# PWR.net
KiCad netlist of a schematic drawn in Altium Designer
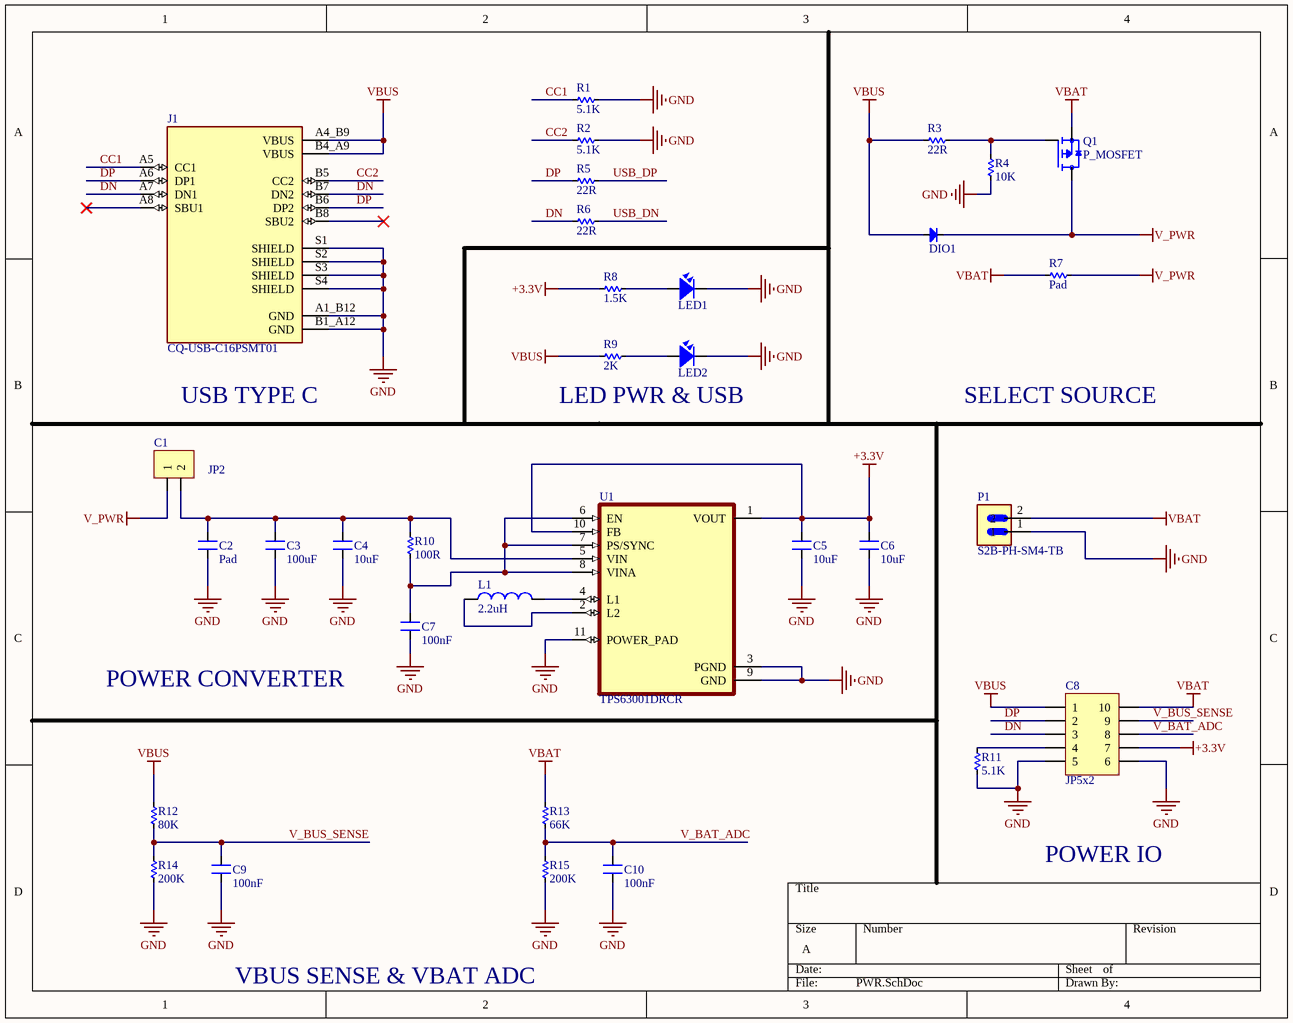
[diagram p0: PWR.SchDoc]

(export (version "E")
  (design (tool "Eeschema 10.0.6"))
  (components
    (comp (ref "C1")
      (value "JP2")
      (footprint "JP2-CLOSED")
      (description "WR-PHD 2.54 mm Angled Socket Header")
      (fields
        (field (name "MANUFACTURER") "Würth Elektronik eiSos GmbH")
        (field (name "PARTNO") "613002143121")
        (field (name "CREATED BY") "Karrer Zheng")
      )
      (libsource (lib "DATN_LIB") (part "JP2"))
    )
    (comp (ref "C2") (value "Pad") (footprint "PAD-SMD-1206") (libsource (lib "DATN_LIB") (part "Cap-SMD")))
    (comp (ref "C3") (value "100uF") (footprint "CN-SMD-1206") (libsource (lib "DATN_LIB") (part "Cap-SMD")))
    (comp (ref "C4") (value "10uF") (footprint "CN-SMD-1206") (libsource (lib "DATN_LIB") (part "Cap-SMD")))
    (comp (ref "C5") (value "10uF") (footprint "CN-SMD-1206") (libsource (lib "DATN_LIB") (part "Cap-SMD")))
    (comp (ref "C6") (value "10uF") (footprint "CN-SMD-1206") (libsource (lib "DATN_LIB") (part "Cap-SMD")))
    (comp (ref "C7") (value "100nF") (footprint "CN-SMD-0603") (libsource (lib "DATN_LIB") (part "Cap-SMD")))
    (comp (ref "C8")
      (value "JP5x2")
      (footprint "JP5-D2T")
      (description "WR-PHD 2.54 mm Dual Socket Header")
      (fields
        (field (name "MANUFACTURER") "Würth Elektronik eiSos GmbH")
        (field (name "PARTNO") "61301021821")
        (field (name "CREATED BY") "Karrer Zheng")
      )
      (libsource (lib "DATN_LIB") (part "JP5x2"))
    )
    (comp (ref "C9") (value "100nF") (footprint "CN-SMD-0603") (libsource (lib "DATN_LIB") (part "Cap-SMD")))
    (comp (ref "C10") (value "100nF") (footprint "CN-SMD-0603") (libsource (lib "DATN_LIB") (part "Cap-SMD")))
    (comp (ref "DIO1")
      (value "Diode SMD")
      (footprint "DIO-SMD-123")
      (description "Default Diode")
      (fields (field (name "PUBLISHER") "Altium Limited"))
      (libsource (lib "DATN_LIB") (part "Diode SMD"))
    )
    (comp (ref "J1")
      (value "CQ-USB-C16PSMT01")
      (footprint "SHENZHEN-CHUANGQIN-TECHNOLOGY_CQ-USB-C16PSMT01")
      (description "C Type USB Type-C Female Plug 16 Pin Connector Power Charger Jack Port")
      (fields (field (name "MF") "Shenzen Chuangqin Technology"))
      (libsource (lib "DATN_LIB") (part "CQ-USB-C16PSMT01"))
    )
    (comp (ref "L1")
      (value "2.2uH")
      (footprint "INDC6060X300")
      (description "INDUCTOR wire-wound")
      (fields (field (name "MP") "LQW2BAN68NG00L"))
      (libsource (lib "DATN_LIB") (part "SMD-Wire-Inductor"))
    )
    (comp (ref "LED1")
      (value "LED GREEN")
      (footprint "LED-0805-Green")
      (libsource (lib "DATN_LIB") (part "LED SMD"))
    )
    (comp (ref "LED2")
      (value "LED GREEN")
      (footprint "LED-0805-Blue")
      (libsource (lib "DATN_LIB") (part "LED SMD"))
    )
    (comp (ref "P1")
      (value "S2B-PH-SM4-TB")
      (footprint "JST_S2B-PH-SM4-TB")
      (description "Connector Header Surface Mount, Right Angle 2 position 0.079 (2.00mm)")
      (fields (field (name "MF") "JST Sales"))
      (libsource (lib "DATN_LIB") (part "S2B-PH-SM4-TB"))
    )
    (comp (ref "Q1")
      (value "P_MOSFET")
      (footprint "P_MOSFET_SOT23")
      (fields (field (name "MF") "Diotec Semiconductor") (field (name "MP") "MMFTP3401"))
      (libsource (lib "DATN_LIB") (part "P_MOSFET"))
    )
    (comp (ref "R1")
      (value "5.1K")
      (footprint "RES-SMD-0603")
      (description "Resistor")
      (fields
        (field (name "MANUFACTURER") "Generic Components")
        (field (name "PUBLISHER") "Altium Hobart Technology Centre")
      )
      (libsource (lib "DATN_LIB") (part "Res-SMD"))
    )
    (comp (ref "R2")
      (value "5.1K")
      (footprint "RES-SMD-0603")
      (description "Resistor")
      (fields
        (field (name "MANUFACTURER") "Generic Components")
        (field (name "PUBLISHER") "Altium Hobart Technology Centre")
      )
      (libsource (lib "DATN_LIB") (part "Res-SMD"))
    )
    (comp (ref "R3")
      (value "22R")
      (footprint "RES-SMD-0603")
      (description "Resistor")
      (fields
        (field (name "MANUFACTURER") "Generic Components")
        (field (name "PUBLISHER") "Altium Hobart Technology Centre")
      )
      (libsource (lib "DATN_LIB") (part "Res-SMD"))
    )
    (comp (ref "R4")
      (value "10K")
      (footprint "RES-SMD-0603")
      (description "Resistor")
      (fields
        (field (name "MANUFACTURER") "Generic Components")
        (field (name "PUBLISHER") "Altium Hobart Technology Centre")
      )
      (libsource (lib "DATN_LIB") (part "Res-SMD"))
    )
    (comp (ref "R5")
      (value "22R")
      (footprint "RES-SMD-0603")
      (description "Resistor")
      (fields
        (field (name "MANUFACTURER") "Generic Components")
        (field (name "PUBLISHER") "Altium Hobart Technology Centre")
      )
      (libsource (lib "DATN_LIB") (part "Res-SMD"))
    )
    (comp (ref "R6")
      (value "22R")
      (footprint "RES-SMD-0603")
      (description "Resistor")
      (fields
        (field (name "MANUFACTURER") "Generic Components")
        (field (name "PUBLISHER") "Altium Hobart Technology Centre")
      )
      (libsource (lib "DATN_LIB") (part "Res-SMD"))
    )
    (comp (ref "R7")
      (value "Pad")
      (footprint "PAD-SMD-1206")
      (description "Resistor")
      (fields
        (field (name "MANUFACTURER") "Generic Components")
        (field (name "PUBLISHER") "Altium Hobart Technology Centre")
      )
      (libsource (lib "DATN_LIB") (part "Res-SMD"))
    )
    (comp (ref "R8")
      (value "1.5K")
      (footprint "RES-SMD-0603")
      (description "Resistor")
      (fields
        (field (name "MANUFACTURER") "Generic Components")
        (field (name "PUBLISHER") "Altium Hobart Technology Centre")
      )
      (libsource (lib "DATN_LIB") (part "Res-SMD"))
    )
    (comp (ref "R9")
      (value "2K")
      (footprint "RES-SMD-0603")
      (description "Resistor")
      (fields
        (field (name "MANUFACTURER") "Generic Components")
        (field (name "PUBLISHER") "Altium Hobart Technology Centre")
      )
      (libsource (lib "DATN_LIB") (part "Res-SMD"))
    )
    (comp (ref "R10")
      (value "100R")
      (footprint "RES-SMD-0603")
      (description "Resistor")
      (fields
        (field (name "MANUFACTURER") "Generic Components")
        (field (name "PUBLISHER") "Altium Hobart Technology Centre")
      )
      (libsource (lib "DATN_LIB") (part "Res-SMD"))
    )
    (comp (ref "R11")
      (value "5.1K")
      (footprint "RES-SMD-0603")
      (description "Resistor")
      (fields
        (field (name "MANUFACTURER") "Generic Components")
        (field (name "PUBLISHER") "Altium Hobart Technology Centre")
      )
      (libsource (lib "DATN_LIB") (part "Res-SMD"))
    )
    (comp (ref "R12")
      (value "80K")
      (footprint "RES-SMD-0603")
      (description "Resistor")
      (fields
        (field (name "MANUFACTURER") "Generic Components")
        (field (name "PUBLISHER") "Altium Hobart Technology Centre")
      )
      (libsource (lib "DATN_LIB") (part "Res-SMD"))
    )
    (comp (ref "R13")
      (value "66K")
      (footprint "RES-SMD-0603")
      (description "Resistor")
      (fields
        (field (name "MANUFACTURER") "Generic Components")
        (field (name "PUBLISHER") "Altium Hobart Technology Centre")
      )
      (libsource (lib "DATN_LIB") (part "Res-SMD"))
    )
    (comp (ref "R14")
      (value "200K")
      (footprint "RES-SMD-0603")
      (description "Resistor")
      (fields
        (field (name "MANUFACTURER") "Generic Components")
        (field (name "PUBLISHER") "Altium Hobart Technology Centre")
      )
      (libsource (lib "DATN_LIB") (part "Res-SMD"))
    )
    (comp (ref "R15")
      (value "200K")
      (footprint "RES-SMD-0603")
      (description "Resistor")
      (fields
        (field (name "MANUFACTURER") "Generic Components")
        (field (name "PUBLISHER") "Altium Hobart Technology Centre")
      )
      (libsource (lib "DATN_LIB") (part "Res-SMD"))
    )
    (comp (ref "U1")
      (value "TPS63001DRCR")
      (footprint "VREG_V62/16624-01YE")
      (description "96% Buck-Boost Converter with 1.7A Current Switches, 3.3V fixed Output voltage in 3x3 QFN")
      (fields (field (name "MF") "Texas Instruments"))
      (libsource (lib "DATN_LIB") (part "TPS63001DRCR"))
    )
  )
  (nets
    (net (code "1") (name "+3.3V") (class "Default")
      (node (ref "C5") (pin "2") (pinfunction "2_2") (pintype "passive"))
      (node (ref "C6") (pin "2") (pinfunction "2_2") (pintype "passive"))
      (node (ref "C8") (pin "7") (pinfunction "7_7") (pintype "passive"))
      (node (ref "R8") (pin "2") (pinfunction "2_2") (pintype "passive"))
      (node (ref "U1") (pin "1") (pinfunction "VOUT_1") (pintype "power_in"))
      (node (ref "U1") (pin "10") (pinfunction "FB_10") (pintype "input"))
    )
    (net (code "2") (name "/CC1") (class "Default")
      (node (ref "J1") (pin "A5") (pinfunction "CC1_A5") (pintype "bidirectional"))
      (node (ref "R1") (pin "2") (pinfunction "2_2") (pintype "passive"))
    )
    (net (code "3") (name "/CC2") (class "Default")
      (node (ref "J1") (pin "B5") (pinfunction "CC2_B5") (pintype "bidirectional"))
      (node (ref "R2") (pin "2") (pinfunction "2_2") (pintype "passive"))
    )
    (net (code "4") (name "/DN") (class "Default")
      (node (ref "C8") (pin "3") (pinfunction "3_3") (pintype "passive"))
      (node (ref "J1") (pin "A7") (pinfunction "DN1_A7") (pintype "bidirectional"))
      (node (ref "J1") (pin "B7") (pinfunction "DN2_B7") (pintype "bidirectional"))
      (node (ref "R6") (pin "2") (pinfunction "2_2") (pintype "passive"))
    )
    (net (code "5") (name "/DP") (class "Default")
      (node (ref "C8") (pin "2") (pinfunction "2_2") (pintype "passive"))
      (node (ref "J1") (pin "A6") (pinfunction "DP1_A6") (pintype "bidirectional"))
      (node (ref "J1") (pin "B6") (pinfunction "DP2_B6") (pintype "bidirectional"))
      (node (ref "R5") (pin "2") (pinfunction "2_2") (pintype "passive"))
    )
    (net (code "6") (name "/USB_DN") (class "Default")
      (node (ref "R6") (pin "1") (pinfunction "1_1") (pintype "passive"))
    )
    (net (code "7") (name "/USB_DP") (class "Default")
      (node (ref "R5") (pin "1") (pinfunction "1_1") (pintype "passive"))
    )
    (net (code "8") (name "/V_BAT_ADC") (class "Default")
      (node (ref "C10") (pin "2") (pinfunction "2_2") (pintype "passive"))
      (node (ref "C8") (pin "8") (pinfunction "8_8") (pintype "passive"))
      (node (ref "R13") (pin "1") (pinfunction "1_1") (pintype "passive"))
      (node (ref "R15") (pin "2") (pinfunction "2_2") (pintype "passive"))
    )
    (net (code "9") (name "/V_BUS_SENSE") (class "Default")
      (node (ref "C8") (pin "9") (pinfunction "9_9") (pintype "passive"))
      (node (ref "C9") (pin "2") (pinfunction "2_2") (pintype "passive"))
      (node (ref "R12") (pin "1") (pinfunction "1_1") (pintype "passive"))
      (node (ref "R14") (pin "2") (pinfunction "2_2") (pintype "passive"))
    )
    (net (code "10") (name "GND") (class "Default")
      (node (ref "C10") (pin "1") (pinfunction "1_1") (pintype "passive"))
      (node (ref "C2") (pin "1") (pinfunction "1_1") (pintype "passive"))
      (node (ref "C3") (pin "1") (pinfunction "1_1") (pintype "passive"))
      (node (ref "C4") (pin "1") (pinfunction "1_1") (pintype "passive"))
      (node (ref "C5") (pin "1") (pinfunction "1_1") (pintype "passive"))
      (node (ref "C6") (pin "1") (pinfunction "1_1") (pintype "passive"))
      (node (ref "C7") (pin "1") (pinfunction "1_1") (pintype "passive"))
      (node (ref "C8") (pin "5") (pinfunction "5_5") (pintype "passive"))
      (node (ref "C8") (pin "6") (pinfunction "6_6") (pintype "passive"))
      (node (ref "C9") (pin "1") (pinfunction "1_1") (pintype "passive"))
      (node (ref "J1") (pin "A1_B12") (pinfunction "GND_A1_B12") (pintype "power_in"))
      (node (ref "J1") (pin "B1_A12") (pinfunction "GND_B1_A12") (pintype "power_in"))
      (node (ref "J1") (pin "S1") (pinfunction "SHIELD_S1") (pintype "passive"))
      (node (ref "J1") (pin "S2") (pinfunction "SHIELD_S2") (pintype "passive"))
      (node (ref "J1") (pin "S3") (pinfunction "SHIELD_S3") (pintype "passive"))
      (node (ref "J1") (pin "S4") (pinfunction "SHIELD_S4") (pintype "passive"))
      (node (ref "LED1") (pin "2") (pinfunction "2_2") (pintype "passive"))
      (node (ref "LED2") (pin "2") (pinfunction "2_2") (pintype "passive"))
      (node (ref "P1") (pin "1") (pinfunction "1_1") (pintype "passive"))
      (node (ref "R1") (pin "1") (pinfunction "1_1") (pintype "passive"))
      (node (ref "R11") (pin "2") (pinfunction "2_2") (pintype "passive"))
      (node (ref "R14") (pin "1") (pinfunction "1_1") (pintype "passive"))
      (node (ref "R15") (pin "1") (pinfunction "1_1") (pintype "passive"))
      (node (ref "R2") (pin "1") (pinfunction "1_1") (pintype "passive"))
      (node (ref "R4") (pin "2") (pinfunction "2_2") (pintype "passive"))
      (node (ref "U1") (pin "11") (pinfunction "POWER_PAD_11") (pintype "bidirectional"))
      (node (ref "U1") (pin "3") (pinfunction "PGND_3") (pintype "power_in"))
      (node (ref "U1") (pin "9") (pinfunction "GND_9") (pintype "power_in"))
    )
    (net (code "11") (name "Net-(C8-Pad4)") (class "Default")
      (node (ref "C8") (pin "4") (pinfunction "4_4") (pintype "passive"))
      (node (ref "R11") (pin "1") (pinfunction "1_1") (pintype "passive"))
    )
    (net (code "12") (name "Net-(LED1-Pad1)") (class "Default")
      (node (ref "LED1") (pin "1") (pinfunction "1_1") (pintype "passive"))
      (node (ref "R8") (pin "1") (pinfunction "1_1") (pintype "passive"))
    )
    (net (code "13") (name "Net-(LED2-Pad1)") (class "Default")
      (node (ref "LED2") (pin "1") (pinfunction "1_1") (pintype "passive"))
      (node (ref "R9") (pin "1") (pinfunction "1_1") (pintype "passive"))
    )
    (net (code "14") (name "Net-(Q1-G)") (class "Default")
      (node (ref "Q1") (pin "1") (pinfunction "G_1") (pintype "passive"))
      (node (ref "R3") (pin "1") (pinfunction "1_1") (pintype "passive"))
      (node (ref "R4") (pin "1") (pinfunction "1_1") (pintype "passive"))
    )
    (net (code "15") (name "Net-(U1-EN)") (class "Default")
      (node (ref "C7") (pin "2") (pinfunction "2_2") (pintype "passive"))
      (node (ref "R10") (pin "2") (pinfunction "2_2") (pintype "passive"))
      (node (ref "U1") (pin "6") (pinfunction "EN_6") (pintype "input"))
      (node (ref "U1") (pin "7") (pinfunction "PS/SYNC_7") (pintype "input"))
      (node (ref "U1") (pin "8") (pinfunction "VINA_8") (pintype "input"))
    )
    (net (code "16") (name "Net-(U1-L1)") (class "Default")
      (node (ref "L1") (pin "2") (pinfunction "2_2") (pintype "passive"))
      (node (ref "U1") (pin "4") (pinfunction "L1_4") (pintype "bidirectional"))
    )
    (net (code "17") (name "Net-(U1-L2)") (class "Default")
      (node (ref "L1") (pin "1") (pinfunction "1_1") (pintype "passive"))
      (node (ref "U1") (pin "2") (pinfunction "L2_2") (pintype "bidirectional"))
    )
    (net (code "18") (name "Net-(U1-VIN)") (class "Default")
      (node (ref "C1") (pin "2") (pinfunction "2_2") (pintype "passive"))
      (node (ref "C2") (pin "2") (pinfunction "2_2") (pintype "passive"))
      (node (ref "C3") (pin "2") (pinfunction "2_2") (pintype "passive"))
      (node (ref "C4") (pin "2") (pinfunction "2_2") (pintype "passive"))
      (node (ref "R10") (pin "1") (pinfunction "1_1") (pintype "passive"))
      (node (ref "U1") (pin "5") (pinfunction "VIN_5") (pintype "input"))
    )
    (net (code "19") (name "VBAT") (class "Default")
      (node (ref "C8") (pin "10") (pinfunction "10_10") (pintype "passive"))
      (node (ref "P1") (pin "2") (pinfunction "2_2") (pintype "passive"))
      (node (ref "Q1") (pin "2") (pinfunction "S_2") (pintype "passive"))
      (node (ref "R13") (pin "2") (pinfunction "2_2") (pintype "passive"))
      (node (ref "R7") (pin "1") (pinfunction "1_1") (pintype "passive"))
    )
    (net (code "20") (name "VBUS") (class "Default")
      (node (ref "C8") (pin "1") (pinfunction "1_1") (pintype "passive"))
      (node (ref "DIO1") (pin "1") (pinfunction "A_1") (pintype "passive"))
      (node (ref "J1") (pin "A4_B9") (pinfunction "VBUS_A4_B9") (pintype "power_in"))
      (node (ref "J1") (pin "B4_A9") (pinfunction "VBUS_B4_A9") (pintype "power_in"))
      (node (ref "R12") (pin "2") (pinfunction "2_2") (pintype "passive"))
      (node (ref "R3") (pin "2") (pinfunction "2_2") (pintype "passive"))
      (node (ref "R9") (pin "2") (pinfunction "2_2") (pintype "passive"))
    )
    (net (code "21") (name "V_PWR") (class "Default")
      (node (ref "C1") (pin "1") (pinfunction "1_1") (pintype "passive"))
      (node (ref "DIO1") (pin "2") (pinfunction "K_2") (pintype "passive"))
      (node (ref "Q1") (pin "3") (pinfunction "D_3") (pintype "passive"))
      (node (ref "R7") (pin "2") (pinfunction "2_2") (pintype "passive"))
    )
    (net (code "22") (name "unconnected-(J1-SBU1-PadA8)") (class "Default")
      (node (ref "J1") (pin "A8") (pinfunction "SBU1_A8") (pintype "bidirectional+no_connect"))
    )
    (net (code "23") (name "unconnected-(J1-SBU2-PadB8)") (class "Default")
      (node (ref "J1") (pin "B8") (pinfunction "SBU2_B8") (pintype "bidirectional+no_connect"))
    )
  )
)
